# EE02CO2Sensor.net
KiCad netlist of a schematic drawn in EAGLE
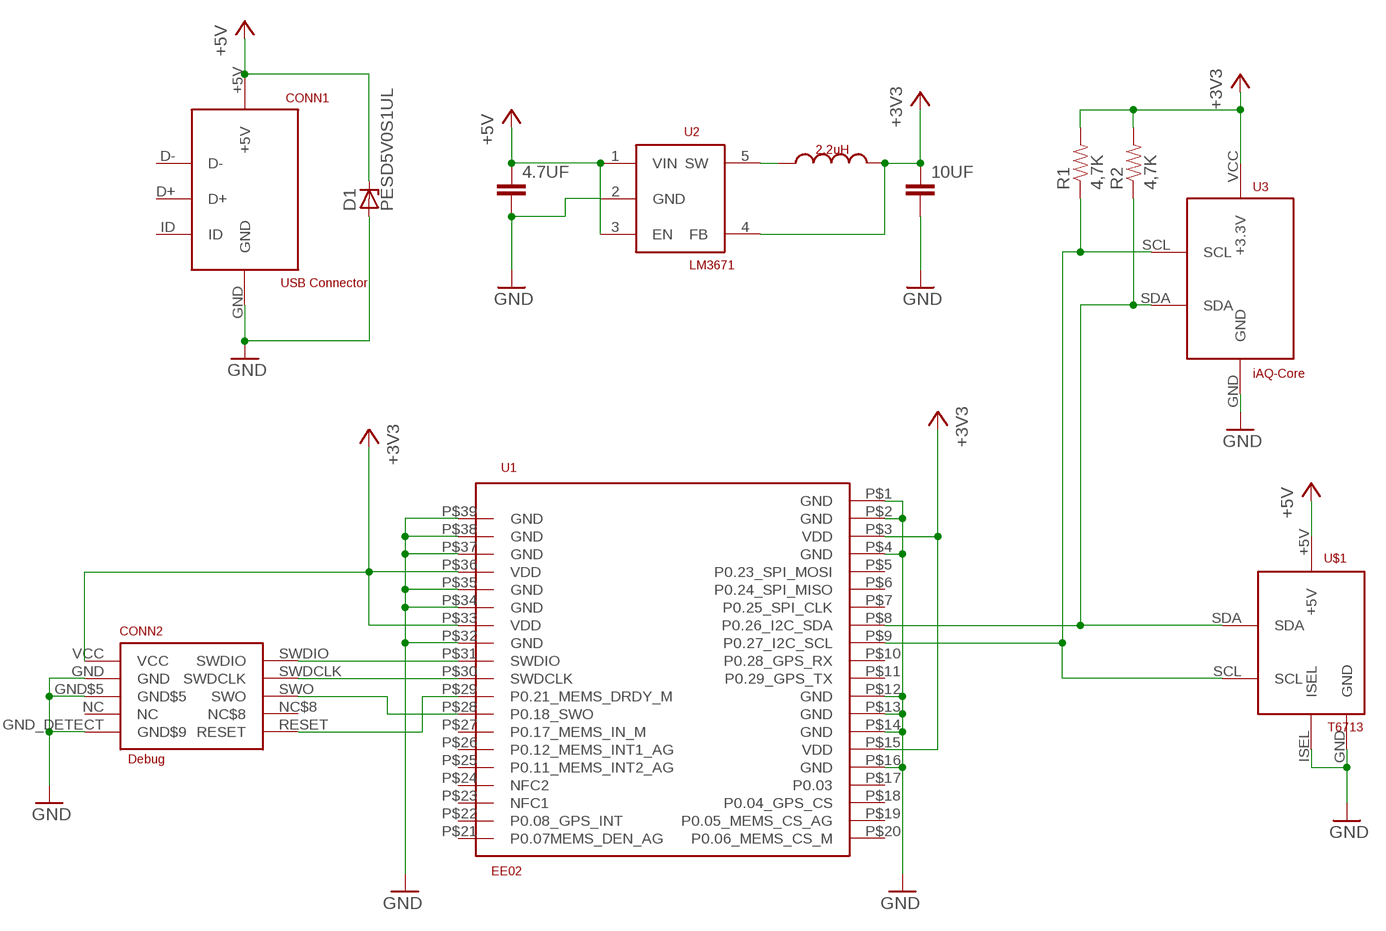
[diagram p0: schematic, sheet 1]

(export (version "E")
  (design (tool "Eeschema 10.0.6"))
  (components
    (comp (ref "4.7UF")
      (value "4.7UF-0805")
      (footprint "eagle-import:0805")
      (libsource (lib "eagle-import") (part "4.7UF-0805"))
    )
    (comp (ref "10UF")
      (value "10UF-1206")
      (footprint "eagle-import:1206")
      (libsource (lib "eagle-import") (part "10UF-1206"))
    )
    (comp (ref "CONN1")
      (value "USB Connector")
      (footprint "eagle-import:USB_MICRO_B")
      (libsource (lib "eagle-import") (part "USB_MICRO_B"))
    )
    (comp (ref "CONN2")
      (value "Debug")
      (footprint "eagle-import:NRF52-P19-CONNECTOR")
      (libsource (lib "eagle-import") (part "DEBUGHEADER"))
    )
    (comp (ref "D1")
      (value "PESD5V0S1UL")
      (footprint "eagle-import:SOD882")
      (libsource (lib "eagle-import") (part "PESD5V0S1UL"))
    )
    (comp (ref "I1")
      (value "2.2uH")
      (footprint "eagle-import:1210")
      (libsource (lib "eagle-import") (part "2.2UH-INDUCTOR-1210"))
    )
    (comp (ref "R1")
      (value "4,7K")
      (footprint "eagle-import:0805")
      (libsource (lib "eagle-import") (part "510OHM1/4W1%(0805)"))
    )
    (comp (ref "R2")
      (value "4,7K")
      (footprint "eagle-import:0805")
      (libsource (lib "eagle-import") (part "510OHM1/4W1%(0805)"))
    )
    (comp (ref "U$1")
      (value "T6713")
      (footprint "eagle-import:T6713CO2")
      (libsource (lib "eagle-import") (part "T6713CO2"))
    )
    (comp (ref "U1")
      (value "EE02")
      (footprint "eagle-import:EE02")
      (libsource (lib "eagle-import") (part "EE02"))
    )
    (comp (ref "U2")
      (value "LM3671")
      (footprint "eagle-import:SOT23-5L")
      (libsource (lib "eagle-import") (part "LM3671"))
    )
    (comp (ref "U3")
      (value "iAQ-Core")
      (footprint "eagle-import:IAQ-CORE")
      (libsource (lib "eagle-import") (part "IAQ-CORE"))
    )
  )
  (nets
    (net (code "1") (name "+3V3") (class "Default")
      (node (ref "10UF") (pin "1") (pinfunction "1_1") (pintype "passive"))
      (node (ref "CONN2") (pin "VCC") (pinfunction "VCC_VCC") (pintype "bidirectional"))
      (node (ref "I1") (pin "2") (pinfunction "2_2") (pintype "passive"))
      (node (ref "R1") (pin "2") (pinfunction "2_2") (pintype "passive"))
      (node (ref "R2") (pin "2") (pinfunction "2_2") (pintype "passive"))
      (node (ref "U1") (pin "P$15") (pinfunction "VDD_P$15") (pintype "bidirectional"))
      (node (ref "U1") (pin "P$3") (pinfunction "VDD_P$3") (pintype "bidirectional"))
      (node (ref "U1") (pin "P$33") (pinfunction "VDD_P$33") (pintype "bidirectional"))
      (node (ref "U1") (pin "P$36") (pinfunction "VDD_P$36") (pintype "bidirectional"))
      (node (ref "U2") (pin "4") (pinfunction "FB_4") (pintype "bidirectional"))
      (node (ref "U3") (pin "VCC") (pinfunction "+3.3V_VCC") (pintype "bidirectional"))
    )
    (net (code "2") (name "+5V") (class "Default")
      (node (ref "4.7UF") (pin "1") (pinfunction "1_1") (pintype "passive"))
      (node (ref "CONN1") (pin "+5V") (pinfunction "+5V_+5V") (pintype "bidirectional"))
      (node (ref "D1") (pin "CATHODE") (pinfunction "C_CATHODE") (pintype "passive"))
      (node (ref "U$1") (pin "+5V") (pinfunction "+5V_+5V") (pintype "bidirectional"))
      (node (ref "U2") (pin "1") (pinfunction "VIN_1") (pintype "bidirectional"))
      (node (ref "U2") (pin "3") (pinfunction "EN_3") (pintype "bidirectional"))
    )
    (net (code "3") (name "GND") (class "Default")
      (node (ref "10UF") (pin "2") (pinfunction "2_2") (pintype "passive"))
      (node (ref "4.7UF") (pin "2") (pinfunction "2_2") (pintype "passive"))
      (node (ref "CONN1") (pin "GND") (pinfunction "GND_GND") (pintype "bidirectional"))
      (node (ref "CONN2") (pin "GND") (pinfunction "GND_GND") (pintype "bidirectional"))
      (node (ref "CONN2") (pin "GND$5") (pinfunction "GND$5_GND$5") (pintype "bidirectional"))
      (node (ref "CONN2") (pin "GND_DETECT") (pinfunction "GND$9_GND_DETECT") (pintype "bidirectional"))
      (node (ref "D1") (pin "ANODE") (pinfunction "A_ANODE") (pintype "passive"))
      (node (ref "U$1") (pin "GND") (pinfunction "GND_GND") (pintype "bidirectional"))
      (node (ref "U$1") (pin "ISEL") (pinfunction "ISEL_ISEL") (pintype "bidirectional"))
      (node (ref "U1") (pin "P$1") (pinfunction "GND_P$1") (pintype "bidirectional"))
      (node (ref "U1") (pin "P$12") (pinfunction "GND_P$12") (pintype "bidirectional"))
      (node (ref "U1") (pin "P$13") (pinfunction "GND_P$13") (pintype "bidirectional"))
      (node (ref "U1") (pin "P$14") (pinfunction "GND_P$14") (pintype "bidirectional"))
      (node (ref "U1") (pin "P$16") (pinfunction "GND_P$16") (pintype "bidirectional"))
      (node (ref "U1") (pin "P$2") (pinfunction "GND_P$2") (pintype "bidirectional"))
      (node (ref "U1") (pin "P$32") (pinfunction "GND_P$32") (pintype "bidirectional"))
      (node (ref "U1") (pin "P$34") (pinfunction "GND_P$34") (pintype "bidirectional"))
      (node (ref "U1") (pin "P$35") (pinfunction "GND_P$35") (pintype "bidirectional"))
      (node (ref "U1") (pin "P$37") (pinfunction "GND_P$37") (pintype "bidirectional"))
      (node (ref "U1") (pin "P$38") (pinfunction "GND_P$38") (pintype "bidirectional"))
      (node (ref "U1") (pin "P$39") (pinfunction "GND_P$39") (pintype "bidirectional"))
      (node (ref "U1") (pin "P$4") (pinfunction "GND_P$4") (pintype "bidirectional"))
      (node (ref "U2") (pin "2") (pinfunction "GND_2") (pintype "bidirectional"))
      (node (ref "U3") (pin "GND") (pinfunction "GND_GND") (pintype "bidirectional"))
    )
    (net (code "4") (name "Net-(U1-P0.18_SWO)") (class "Default")
      (node (ref "CONN2") (pin "SWO") (pinfunction "SWO_SWO") (pintype "bidirectional"))
      (node (ref "U1") (pin "P$28") (pinfunction "P0.18_SWO_P$28") (pintype "bidirectional"))
    )
    (net (code "5") (name "Net-(U1-P0.21_MEMS_DRDY_M)") (class "Default")
      (node (ref "CONN2") (pin "RESET") (pinfunction "RESET_RESET") (pintype "bidirectional"))
      (node (ref "U1") (pin "P$29") (pinfunction "P0.21_MEMS_DRDY_M_P$29") (pintype "bidirectional"))
    )
    (net (code "6") (name "Net-(U1-P0.26_I2C_SDA)") (class "Default")
      (node (ref "R2") (pin "1") (pinfunction "1_1") (pintype "passive"))
      (node (ref "U$1") (pin "SDA") (pinfunction "SDA_SDA") (pintype "bidirectional"))
      (node (ref "U1") (pin "P$8") (pinfunction "P0.26_I2C_SDA_P$8") (pintype "bidirectional"))
      (node (ref "U3") (pin "SDA") (pinfunction "SDA_SDA") (pintype "bidirectional"))
    )
    (net (code "7") (name "Net-(U1-P0.27_I2C_SCL)") (class "Default")
      (node (ref "R1") (pin "1") (pinfunction "1_1") (pintype "passive"))
      (node (ref "U$1") (pin "SCL") (pinfunction "SCL_SCL") (pintype "bidirectional"))
      (node (ref "U1") (pin "P$9") (pinfunction "P0.27_I2C_SCL_P$9") (pintype "bidirectional"))
      (node (ref "U3") (pin "SCL") (pinfunction "SCL_SCL") (pintype "bidirectional"))
    )
    (net (code "8") (name "Net-(U1-SWDCLK)") (class "Default")
      (node (ref "CONN2") (pin "SWDCLK") (pinfunction "SWDCLK_SWDCLK") (pintype "bidirectional"))
      (node (ref "U1") (pin "P$30") (pinfunction "SWDCLK_P$30") (pintype "bidirectional"))
    )
    (net (code "9") (name "Net-(U1-SWDIO)") (class "Default")
      (node (ref "CONN2") (pin "SWDIO") (pinfunction "SWDIO_SWDIO") (pintype "bidirectional"))
      (node (ref "U1") (pin "P$31") (pinfunction "SWDIO_P$31") (pintype "bidirectional"))
    )
    (net (code "10") (name "Net-(U2-SW)") (class "Default")
      (node (ref "I1") (pin "1") (pinfunction "1_1") (pintype "passive"))
      (node (ref "U2") (pin "5") (pinfunction "SW_5") (pintype "bidirectional"))
    )
    (net (code "11") (name "unconnected-(CONN1-PadD+)") (class "Default")
      (node (ref "CONN1") (pin "D+") (pinfunction "D+_D+") (pintype "bidirectional"))
    )
    (net (code "12") (name "unconnected-(CONN1-PadD-)") (class "Default")
      (node (ref "CONN1") (pin "D-") (pinfunction "D-_D-") (pintype "bidirectional"))
    )
    (net (code "13") (name "unconnected-(CONN1-PadID)") (class "Default")
      (node (ref "CONN1") (pin "ID") (pinfunction "ID_ID") (pintype "bidirectional"))
    )
    (net (code "14") (name "unconnected-(CONN2-PadNC$8)") (class "Default")
      (node (ref "CONN2") (pin "NC$8") (pinfunction "NC$8_NC$8") (pintype "bidirectional"))
    )
    (net (code "15") (name "unconnected-(CONN2-PadNC)") (class "Default")
      (node (ref "CONN2") (pin "NC") (pinfunction "NC_NC") (pintype "bidirectional"))
    )
    (net (code "16") (name "unconnected-(U1-NFC1-PadP$23)") (class "Default")
      (node (ref "U1") (pin "P$23") (pinfunction "NFC1_P$23") (pintype "bidirectional"))
    )
    (net (code "17") (name "unconnected-(U1-NFC2-PadP$24)") (class "Default")
      (node (ref "U1") (pin "P$24") (pinfunction "NFC2_P$24") (pintype "bidirectional"))
    )
    (net (code "18") (name "unconnected-(U1-P0.03-PadP$17)") (class "Default")
      (node (ref "U1") (pin "P$17") (pinfunction "P0.03_P$17") (pintype "bidirectional"))
    )
    (net (code "19") (name "unconnected-(U1-P0.04_GPS_CS-PadP$18)") (class "Default")
      (node (ref "U1") (pin "P$18") (pinfunction "P0.04_GPS_CS_P$18") (pintype "bidirectional"))
    )
    (net (code "20") (name "unconnected-(U1-P0.05_MEMS_CS_AG-PadP$19)") (class "Default")
      (node (ref "U1") (pin "P$19") (pinfunction "P0.05_MEMS_CS_AG_P$19") (pintype "bidirectional"))
    )
    (net (code "21") (name "unconnected-(U1-P0.06_MEMS_CS_M-PadP$20)") (class "Default")
      (node (ref "U1") (pin "P$20") (pinfunction "P0.06_MEMS_CS_M_P$20") (pintype "bidirectional"))
    )
    (net (code "22") (name "unconnected-(U1-P0.07MEMS_DEN_AG-PadP$21)") (class "Default")
      (node (ref "U1") (pin "P$21") (pinfunction "P0.07MEMS_DEN_AG_P$21") (pintype "bidirectional"))
    )
    (net (code "23") (name "unconnected-(U1-P0.08_GPS_INT-PadP$22)") (class "Default")
      (node (ref "U1") (pin "P$22") (pinfunction "P0.08_GPS_INT_P$22") (pintype "bidirectional"))
    )
    (net (code "24") (name "unconnected-(U1-P0.11_MEMS_INT2_AG-PadP$25)") (class "Default")
      (node (ref "U1") (pin "P$25") (pinfunction "P0.11_MEMS_INT2_AG_P$25") (pintype "bidirectional"))
    )
    (net (code "25") (name "unconnected-(U1-P0.12_MEMS_INT1_AG-PadP$26)") (class "Default")
      (node (ref "U1") (pin "P$26") (pinfunction "P0.12_MEMS_INT1_AG_P$26") (pintype "bidirectional"))
    )
    (net (code "26") (name "unconnected-(U1-P0.17_MEMS_IN_M-PadP$27)") (class "Default")
      (node (ref "U1") (pin "P$27") (pinfunction "P0.17_MEMS_IN_M_P$27") (pintype "bidirectional"))
    )
    (net (code "27") (name "unconnected-(U1-P0.23_SPI_MOSI-PadP$5)") (class "Default")
      (node (ref "U1") (pin "P$5") (pinfunction "P0.23_SPI_MOSI_P$5") (pintype "bidirectional"))
    )
    (net (code "28") (name "unconnected-(U1-P0.24_SPI_MISO-PadP$6)") (class "Default")
      (node (ref "U1") (pin "P$6") (pinfunction "P0.24_SPI_MISO_P$6") (pintype "bidirectional"))
    )
    (net (code "29") (name "unconnected-(U1-P0.25_SPI_CLK-PadP$7)") (class "Default")
      (node (ref "U1") (pin "P$7") (pinfunction "P0.25_SPI_CLK_P$7") (pintype "bidirectional"))
    )
    (net (code "30") (name "unconnected-(U1-P0.28_GPS_RX-PadP$10)") (class "Default")
      (node (ref "U1") (pin "P$10") (pinfunction "P0.28_GPS_RX_P$10") (pintype "bidirectional"))
    )
    (net (code "31") (name "unconnected-(U1-P0.29_GPS_TX-PadP$11)") (class "Default")
      (node (ref "U1") (pin "P$11") (pinfunction "P0.29_GPS_TX_P$11") (pintype "bidirectional"))
    )
  )
)
